# relais.net
KiCad netlist of a schematic drawn in Altium Designer
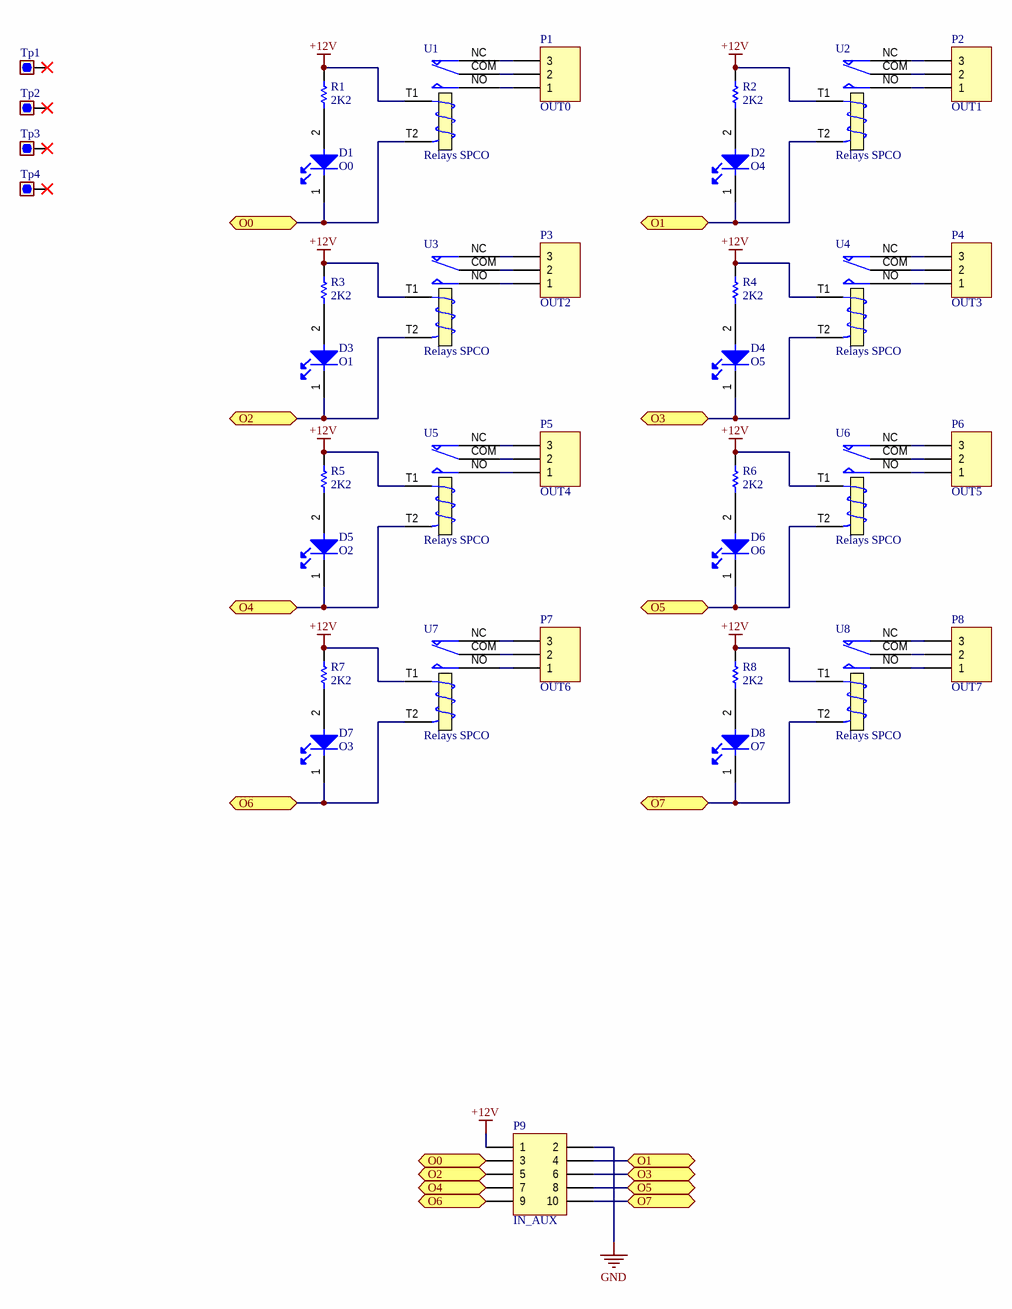
[diagram p0: relais.SchDoc]

(export (version "E")
  (design (tool "Eeschema 10.0.6"))
  (components
    (comp (ref "D1")
      (value "O0")
      (footprint "0805_[2012]_LED")
      (description "Multicolor LED")
      (libsource (lib "DEVELER_Library") (part "LED"))
    )
    (comp (ref "D2")
      (value "O4")
      (footprint "0805_[2012]_LED")
      (description "Multicolor LED")
      (libsource (lib "DEVELER_Library") (part "LED"))
    )
    (comp (ref "D3")
      (value "O1")
      (footprint "0805_[2012]_LED")
      (description "Multicolor LED")
      (libsource (lib "DEVELER_Library") (part "LED"))
    )
    (comp (ref "D4")
      (value "O5")
      (footprint "0805_[2012]_LED")
      (description "Multicolor LED")
      (libsource (lib "DEVELER_Library") (part "LED"))
    )
    (comp (ref "D5")
      (value "O2")
      (footprint "0805_[2012]_LED")
      (description "Multicolor LED")
      (libsource (lib "DEVELER_Library") (part "LED"))
    )
    (comp (ref "D6")
      (value "O6")
      (footprint "0805_[2012]_LED")
      (description "Multicolor LED")
      (libsource (lib "DEVELER_Library") (part "LED"))
    )
    (comp (ref "D7")
      (value "O3")
      (footprint "0805_[2012]_LED")
      (description "Multicolor LED")
      (libsource (lib "DEVELER_Library") (part "LED"))
    )
    (comp (ref "D8")
      (value "O7")
      (footprint "0805_[2012]_LED")
      (description "Multicolor LED")
      (libsource (lib "DEVELER_Library") (part "LED"))
    )
    (comp (ref "P1")
      (value "OUT0")
      (footprint "TBLOCK_1X3_5.08MM_THD")
      (description "Header, 3-Pin")
      (fields (field (name "PUBLISHER") "Altium Limited"))
      (libsource (lib "Miscellaneous Connectors") (part "Header 3"))
    )
    (comp (ref "P2")
      (value "OUT1")
      (footprint "TBLOCK_1X3_5.08MM_THD")
      (description "Header, 3-Pin")
      (fields (field (name "PUBLISHER") "Altium Limited"))
      (libsource (lib "Miscellaneous Connectors") (part "Header 3"))
    )
    (comp (ref "P3")
      (value "OUT2")
      (footprint "TBLOCK_1X3_5.08MM_THD")
      (description "Header, 3-Pin")
      (fields (field (name "PUBLISHER") "Altium Limited"))
      (libsource (lib "Miscellaneous Connectors") (part "Header 3"))
    )
    (comp (ref "P4")
      (value "OUT3")
      (footprint "TBLOCK_1X3_5.08MM_THD")
      (description "Header, 3-Pin")
      (fields (field (name "PUBLISHER") "Altium Limited"))
      (libsource (lib "Miscellaneous Connectors") (part "Header 3"))
    )
    (comp (ref "P5")
      (value "OUT4")
      (footprint "TBLOCK_1X3_5.08MM_THD")
      (description "Header, 3-Pin")
      (fields (field (name "PUBLISHER") "Altium Limited"))
      (libsource (lib "Miscellaneous Connectors") (part "Header 3"))
    )
    (comp (ref "P6")
      (value "OUT5")
      (footprint "TBLOCK_1X3_5.08MM_THD")
      (description "Header, 3-Pin")
      (fields (field (name "PUBLISHER") "Altium Limited"))
      (libsource (lib "Miscellaneous Connectors") (part "Header 3"))
    )
    (comp (ref "P7")
      (value "OUT6")
      (footprint "TBLOCK_1X3_5.08MM_THD")
      (description "Header, 3-Pin")
      (fields (field (name "PUBLISHER") "Altium Limited"))
      (libsource (lib "Miscellaneous Connectors") (part "Header 3"))
    )
    (comp (ref "P8")
      (value "OUT7")
      (footprint "TBLOCK_1X3_5.08MM_THD")
      (description "Header, 3-Pin")
      (fields (field (name "PUBLISHER") "Altium Limited"))
      (libsource (lib "Miscellaneous Connectors") (part "Header 3"))
    )
    (comp (ref "P9")
      (value "IN_AUX")
      (footprint "HEADER_2X5_2.54MM_THD_BOXED")
      (description "Header, 5-Pin, Dual row")
      (fields (field (name "PUBLISHER") "Altium Limited"))
      (libsource (lib "Miscellaneous Connectors") (part "Header 5X2"))
    )
    (comp (ref "R1")
      (value "2K2")
      (footprint "0603_[1608]")
      (description "Resistor")
      (libsource (lib "DEVELER_Library") (part "Res1"))
    )
    (comp (ref "R2")
      (value "2K2")
      (footprint "0603_[1608]")
      (description "Resistor")
      (libsource (lib "DEVELER_Library") (part "Res1"))
    )
    (comp (ref "R3")
      (value "2K2")
      (footprint "0603_[1608]")
      (description "Resistor")
      (libsource (lib "DEVELER_Library") (part "Res1"))
    )
    (comp (ref "R4")
      (value "2K2")
      (footprint "0603_[1608]")
      (description "Resistor")
      (libsource (lib "DEVELER_Library") (part "Res1"))
    )
    (comp (ref "R5")
      (value "2K2")
      (footprint "0603_[1608]")
      (description "Resistor")
      (libsource (lib "DEVELER_Library") (part "Res1"))
    )
    (comp (ref "R6")
      (value "2K2")
      (footprint "0603_[1608]")
      (description "Resistor")
      (libsource (lib "DEVELER_Library") (part "Res1"))
    )
    (comp (ref "R7")
      (value "2K2")
      (footprint "0603_[1608]")
      (description "Resistor")
      (libsource (lib "DEVELER_Library") (part "Res1"))
    )
    (comp (ref "R8")
      (value "2K2")
      (footprint "0603_[1608]")
      (description "Resistor")
      (libsource (lib "DEVELER_Library") (part "Res1"))
    )
    (comp (ref "Tp1")
      (value "~")
      (footprint "Hole_M3x6mm")
      (libsource (lib "DEVELER_Library") (part "Test_point"))
    )
    (comp (ref "Tp2")
      (value "~")
      (footprint "Hole_M3x6mm")
      (libsource (lib "DEVELER_Library") (part "Test_point"))
    )
    (comp (ref "Tp3")
      (value "~")
      (footprint "Hole_M3x6mm")
      (libsource (lib "DEVELER_Library") (part "Test_point"))
    )
    (comp (ref "Tp4")
      (value "~")
      (footprint "Hole_M3x6mm")
      (libsource (lib "DEVELER_Library") (part "Test_point"))
    )
    (comp (ref "U1")
      (value "Relays SPCO")
      (footprint "RELAYS_SPCO_THD_20x10mirror")
      (libsource (lib "develer_library") (part "Relay SPCO"))
    )
    (comp (ref "U2")
      (value "Relays SPCO")
      (footprint "RELAYS_SPCO_THD_20x10mirror")
      (libsource (lib "develer_library") (part "Relay SPCO"))
    )
    (comp (ref "U3")
      (value "Relays SPCO")
      (footprint "RELAYS_SPCO_THD_20x10mirror")
      (libsource (lib "develer_library") (part "Relay SPCO"))
    )
    (comp (ref "U4")
      (value "Relays SPCO")
      (footprint "RELAYS_SPCO_THD_20x10mirror")
      (libsource (lib "develer_library") (part "Relay SPCO"))
    )
    (comp (ref "U5")
      (value "Relays SPCO")
      (footprint "RELAYS_SPCO_THD_20x10mirror")
      (libsource (lib "develer_library") (part "Relay SPCO"))
    )
    (comp (ref "U6")
      (value "Relays SPCO")
      (footprint "RELAYS_SPCO_THD_20x10mirror")
      (libsource (lib "develer_library") (part "Relay SPCO"))
    )
    (comp (ref "U7")
      (value "Relays SPCO")
      (footprint "RELAYS_SPCO_THD_20x10mirror")
      (libsource (lib "develer_library") (part "Relay SPCO"))
    )
    (comp (ref "U8")
      (value "Relays SPCO")
      (footprint "RELAYS_SPCO_THD_20x10mirror")
      (libsource (lib "develer_library") (part "Relay SPCO"))
    )
  )
  (nets
    (net (code "1") (name "+12V") (class "Default")
      (node (ref "P9") (pin "1") (pinfunction "1_1") (pintype "passive"))
      (node (ref "R1") (pin "2") (pinfunction "2_2") (pintype "passive"))
      (node (ref "R2") (pin "2") (pinfunction "2_2") (pintype "passive"))
      (node (ref "R3") (pin "2") (pinfunction "2_2") (pintype "passive"))
      (node (ref "R4") (pin "2") (pinfunction "2_2") (pintype "passive"))
      (node (ref "R5") (pin "2") (pinfunction "2_2") (pintype "passive"))
      (node (ref "R6") (pin "2") (pinfunction "2_2") (pintype "passive"))
      (node (ref "R7") (pin "2") (pinfunction "2_2") (pintype "passive"))
      (node (ref "R8") (pin "2") (pinfunction "2_2") (pintype "passive"))
      (node (ref "U1") (pin "T1") (pinfunction "T1_T1") (pintype "passive"))
      (node (ref "U2") (pin "T1") (pinfunction "T1_T1") (pintype "passive"))
      (node (ref "U3") (pin "T1") (pinfunction "T1_T1") (pintype "passive"))
      (node (ref "U4") (pin "T1") (pinfunction "T1_T1") (pintype "passive"))
      (node (ref "U5") (pin "T1") (pinfunction "T1_T1") (pintype "passive"))
      (node (ref "U6") (pin "T1") (pinfunction "T1_T1") (pintype "passive"))
      (node (ref "U7") (pin "T1") (pinfunction "T1_T1") (pintype "passive"))
      (node (ref "U8") (pin "T1") (pinfunction "T1_T1") (pintype "passive"))
    )
    (net (code "2") (name "/O0") (class "Default")
      (node (ref "D1") (pin "1") (pinfunction "K_1") (pintype "passive"))
      (node (ref "P9") (pin "3") (pinfunction "3_3") (pintype "passive"))
      (node (ref "U1") (pin "T2") (pinfunction "T2_T2") (pintype "passive"))
    )
    (net (code "3") (name "/O1") (class "Default")
      (node (ref "D2") (pin "1") (pinfunction "K_1") (pintype "passive"))
      (node (ref "P9") (pin "4") (pinfunction "4_4") (pintype "passive"))
      (node (ref "U2") (pin "T2") (pinfunction "T2_T2") (pintype "passive"))
    )
    (net (code "4") (name "/O2") (class "Default")
      (node (ref "D3") (pin "1") (pinfunction "K_1") (pintype "passive"))
      (node (ref "P9") (pin "5") (pinfunction "5_5") (pintype "passive"))
      (node (ref "U3") (pin "T2") (pinfunction "T2_T2") (pintype "passive"))
    )
    (net (code "5") (name "/O3") (class "Default")
      (node (ref "D4") (pin "1") (pinfunction "K_1") (pintype "passive"))
      (node (ref "P9") (pin "6") (pinfunction "6_6") (pintype "passive"))
      (node (ref "U4") (pin "T2") (pinfunction "T2_T2") (pintype "passive"))
    )
    (net (code "6") (name "/O4") (class "Default")
      (node (ref "D5") (pin "1") (pinfunction "K_1") (pintype "passive"))
      (node (ref "P9") (pin "7") (pinfunction "7_7") (pintype "passive"))
      (node (ref "U5") (pin "T2") (pinfunction "T2_T2") (pintype "passive"))
    )
    (net (code "7") (name "/O5") (class "Default")
      (node (ref "D6") (pin "1") (pinfunction "K_1") (pintype "passive"))
      (node (ref "P9") (pin "8") (pinfunction "8_8") (pintype "passive"))
      (node (ref "U6") (pin "T2") (pinfunction "T2_T2") (pintype "passive"))
    )
    (net (code "8") (name "/O6") (class "Default")
      (node (ref "D7") (pin "1") (pinfunction "K_1") (pintype "passive"))
      (node (ref "P9") (pin "9") (pinfunction "9_9") (pintype "passive"))
      (node (ref "U7") (pin "T2") (pinfunction "T2_T2") (pintype "passive"))
    )
    (net (code "9") (name "/O7") (class "Default")
      (node (ref "D8") (pin "1") (pinfunction "K_1") (pintype "passive"))
      (node (ref "P9") (pin "10") (pinfunction "10_10") (pintype "passive"))
      (node (ref "U8") (pin "T2") (pinfunction "T2_T2") (pintype "passive"))
    )
    (net (code "10") (name "GND") (class "Default")
      (node (ref "P9") (pin "2") (pinfunction "2_2") (pintype "passive"))
    )
    (net (code "11") (name "Net-(D1-A)") (class "Default")
      (node (ref "D1") (pin "2") (pinfunction "A_2") (pintype "passive"))
      (node (ref "R1") (pin "1") (pinfunction "1_1") (pintype "passive"))
    )
    (net (code "12") (name "Net-(D2-A)") (class "Default")
      (node (ref "D2") (pin "2") (pinfunction "A_2") (pintype "passive"))
      (node (ref "R2") (pin "1") (pinfunction "1_1") (pintype "passive"))
    )
    (net (code "13") (name "Net-(D3-A)") (class "Default")
      (node (ref "D3") (pin "2") (pinfunction "A_2") (pintype "passive"))
      (node (ref "R3") (pin "1") (pinfunction "1_1") (pintype "passive"))
    )
    (net (code "14") (name "Net-(D4-A)") (class "Default")
      (node (ref "D4") (pin "2") (pinfunction "A_2") (pintype "passive"))
      (node (ref "R4") (pin "1") (pinfunction "1_1") (pintype "passive"))
    )
    (net (code "15") (name "Net-(D5-A)") (class "Default")
      (node (ref "D5") (pin "2") (pinfunction "A_2") (pintype "passive"))
      (node (ref "R5") (pin "1") (pinfunction "1_1") (pintype "passive"))
    )
    (net (code "16") (name "Net-(D6-A)") (class "Default")
      (node (ref "D6") (pin "2") (pinfunction "A_2") (pintype "passive"))
      (node (ref "R6") (pin "1") (pinfunction "1_1") (pintype "passive"))
    )
    (net (code "17") (name "Net-(D7-A)") (class "Default")
      (node (ref "D7") (pin "2") (pinfunction "A_2") (pintype "passive"))
      (node (ref "R7") (pin "1") (pinfunction "1_1") (pintype "passive"))
    )
    (net (code "18") (name "Net-(D8-A)") (class "Default")
      (node (ref "D8") (pin "2") (pinfunction "A_2") (pintype "passive"))
      (node (ref "R8") (pin "1") (pinfunction "1_1") (pintype "passive"))
    )
    (net (code "19") (name "Net-(P1-Pad1)") (class "Default")
      (node (ref "P1") (pin "1") (pinfunction "1_1") (pintype "passive"))
      (node (ref "U1") (pin "NO") (pinfunction "NO_NO") (pintype "passive"))
    )
    (net (code "20") (name "Net-(P1-Pad2)") (class "Default")
      (node (ref "P1") (pin "2") (pinfunction "2_2") (pintype "passive"))
      (node (ref "U1") (pin "COM") (pinfunction "COM_COM") (pintype "passive"))
    )
    (net (code "21") (name "Net-(P1-Pad3)") (class "Default")
      (node (ref "P1") (pin "3") (pinfunction "3_3") (pintype "passive"))
      (node (ref "U1") (pin "NC") (pinfunction "NC_NC") (pintype "passive"))
    )
    (net (code "22") (name "Net-(P2-Pad1)") (class "Default")
      (node (ref "P2") (pin "1") (pinfunction "1_1") (pintype "passive"))
      (node (ref "U2") (pin "NO") (pinfunction "NO_NO") (pintype "passive"))
    )
    (net (code "23") (name "Net-(P2-Pad2)") (class "Default")
      (node (ref "P2") (pin "2") (pinfunction "2_2") (pintype "passive"))
      (node (ref "U2") (pin "COM") (pinfunction "COM_COM") (pintype "passive"))
    )
    (net (code "24") (name "Net-(P2-Pad3)") (class "Default")
      (node (ref "P2") (pin "3") (pinfunction "3_3") (pintype "passive"))
      (node (ref "U2") (pin "NC") (pinfunction "NC_NC") (pintype "passive"))
    )
    (net (code "25") (name "Net-(P3-Pad1)") (class "Default")
      (node (ref "P3") (pin "1") (pinfunction "1_1") (pintype "passive"))
      (node (ref "U3") (pin "NO") (pinfunction "NO_NO") (pintype "passive"))
    )
    (net (code "26") (name "Net-(P3-Pad2)") (class "Default")
      (node (ref "P3") (pin "2") (pinfunction "2_2") (pintype "passive"))
      (node (ref "U3") (pin "COM") (pinfunction "COM_COM") (pintype "passive"))
    )
    (net (code "27") (name "Net-(P3-Pad3)") (class "Default")
      (node (ref "P3") (pin "3") (pinfunction "3_3") (pintype "passive"))
      (node (ref "U3") (pin "NC") (pinfunction "NC_NC") (pintype "passive"))
    )
    (net (code "28") (name "Net-(P4-Pad1)") (class "Default")
      (node (ref "P4") (pin "1") (pinfunction "1_1") (pintype "passive"))
      (node (ref "U4") (pin "NO") (pinfunction "NO_NO") (pintype "passive"))
    )
    (net (code "29") (name "Net-(P4-Pad2)") (class "Default")
      (node (ref "P4") (pin "2") (pinfunction "2_2") (pintype "passive"))
      (node (ref "U4") (pin "COM") (pinfunction "COM_COM") (pintype "passive"))
    )
    (net (code "30") (name "Net-(P4-Pad3)") (class "Default")
      (node (ref "P4") (pin "3") (pinfunction "3_3") (pintype "passive"))
      (node (ref "U4") (pin "NC") (pinfunction "NC_NC") (pintype "passive"))
    )
    (net (code "31") (name "Net-(P5-Pad1)") (class "Default")
      (node (ref "P5") (pin "1") (pinfunction "1_1") (pintype "passive"))
      (node (ref "U5") (pin "NO") (pinfunction "NO_NO") (pintype "passive"))
    )
    (net (code "32") (name "Net-(P5-Pad2)") (class "Default")
      (node (ref "P5") (pin "2") (pinfunction "2_2") (pintype "passive"))
      (node (ref "U5") (pin "COM") (pinfunction "COM_COM") (pintype "passive"))
    )
    (net (code "33") (name "Net-(P5-Pad3)") (class "Default")
      (node (ref "P5") (pin "3") (pinfunction "3_3") (pintype "passive"))
      (node (ref "U5") (pin "NC") (pinfunction "NC_NC") (pintype "passive"))
    )
    (net (code "34") (name "Net-(P6-Pad1)") (class "Default")
      (node (ref "P6") (pin "1") (pinfunction "1_1") (pintype "passive"))
      (node (ref "U6") (pin "NO") (pinfunction "NO_NO") (pintype "passive"))
    )
    (net (code "35") (name "Net-(P6-Pad2)") (class "Default")
      (node (ref "P6") (pin "2") (pinfunction "2_2") (pintype "passive"))
      (node (ref "U6") (pin "COM") (pinfunction "COM_COM") (pintype "passive"))
    )
    (net (code "36") (name "Net-(P6-Pad3)") (class "Default")
      (node (ref "P6") (pin "3") (pinfunction "3_3") (pintype "passive"))
      (node (ref "U6") (pin "NC") (pinfunction "NC_NC") (pintype "passive"))
    )
    (net (code "37") (name "Net-(P7-Pad1)") (class "Default")
      (node (ref "P7") (pin "1") (pinfunction "1_1") (pintype "passive"))
      (node (ref "U7") (pin "NO") (pinfunction "NO_NO") (pintype "passive"))
    )
    (net (code "38") (name "Net-(P7-Pad2)") (class "Default")
      (node (ref "P7") (pin "2") (pinfunction "2_2") (pintype "passive"))
      (node (ref "U7") (pin "COM") (pinfunction "COM_COM") (pintype "passive"))
    )
    (net (code "39") (name "Net-(P7-Pad3)") (class "Default")
      (node (ref "P7") (pin "3") (pinfunction "3_3") (pintype "passive"))
      (node (ref "U7") (pin "NC") (pinfunction "NC_NC") (pintype "passive"))
    )
    (net (code "40") (name "Net-(P8-Pad1)") (class "Default")
      (node (ref "P8") (pin "1") (pinfunction "1_1") (pintype "passive"))
      (node (ref "U8") (pin "NO") (pinfunction "NO_NO") (pintype "passive"))
    )
    (net (code "41") (name "Net-(P8-Pad2)") (class "Default")
      (node (ref "P8") (pin "2") (pinfunction "2_2") (pintype "passive"))
      (node (ref "U8") (pin "COM") (pinfunction "COM_COM") (pintype "passive"))
    )
    (net (code "42") (name "Net-(P8-Pad3)") (class "Default")
      (node (ref "P8") (pin "3") (pinfunction "3_3") (pintype "passive"))
      (node (ref "U8") (pin "NC") (pinfunction "NC_NC") (pintype "passive"))
    )
    (net (code "43") (name "unconnected-(Tp1-Pad1)") (class "Default")
      (node (ref "Tp1") (pin "1") (pinfunction "1_1") (pintype "passive+no_connect"))
    )
    (net (code "44") (name "unconnected-(Tp2-Pad1)") (class "Default")
      (node (ref "Tp2") (pin "1") (pinfunction "1_1") (pintype "passive+no_connect"))
    )
    (net (code "45") (name "unconnected-(Tp3-Pad1)") (class "Default")
      (node (ref "Tp3") (pin "1") (pinfunction "1_1") (pintype "passive+no_connect"))
    )
    (net (code "46") (name "unconnected-(Tp4-Pad1)") (class "Default")
      (node (ref "Tp4") (pin "1") (pinfunction "1_1") (pintype "passive+no_connect"))
    )
  )
)
